# PAGE1.net
KiCad netlist of a schematic drawn in Altium Designer
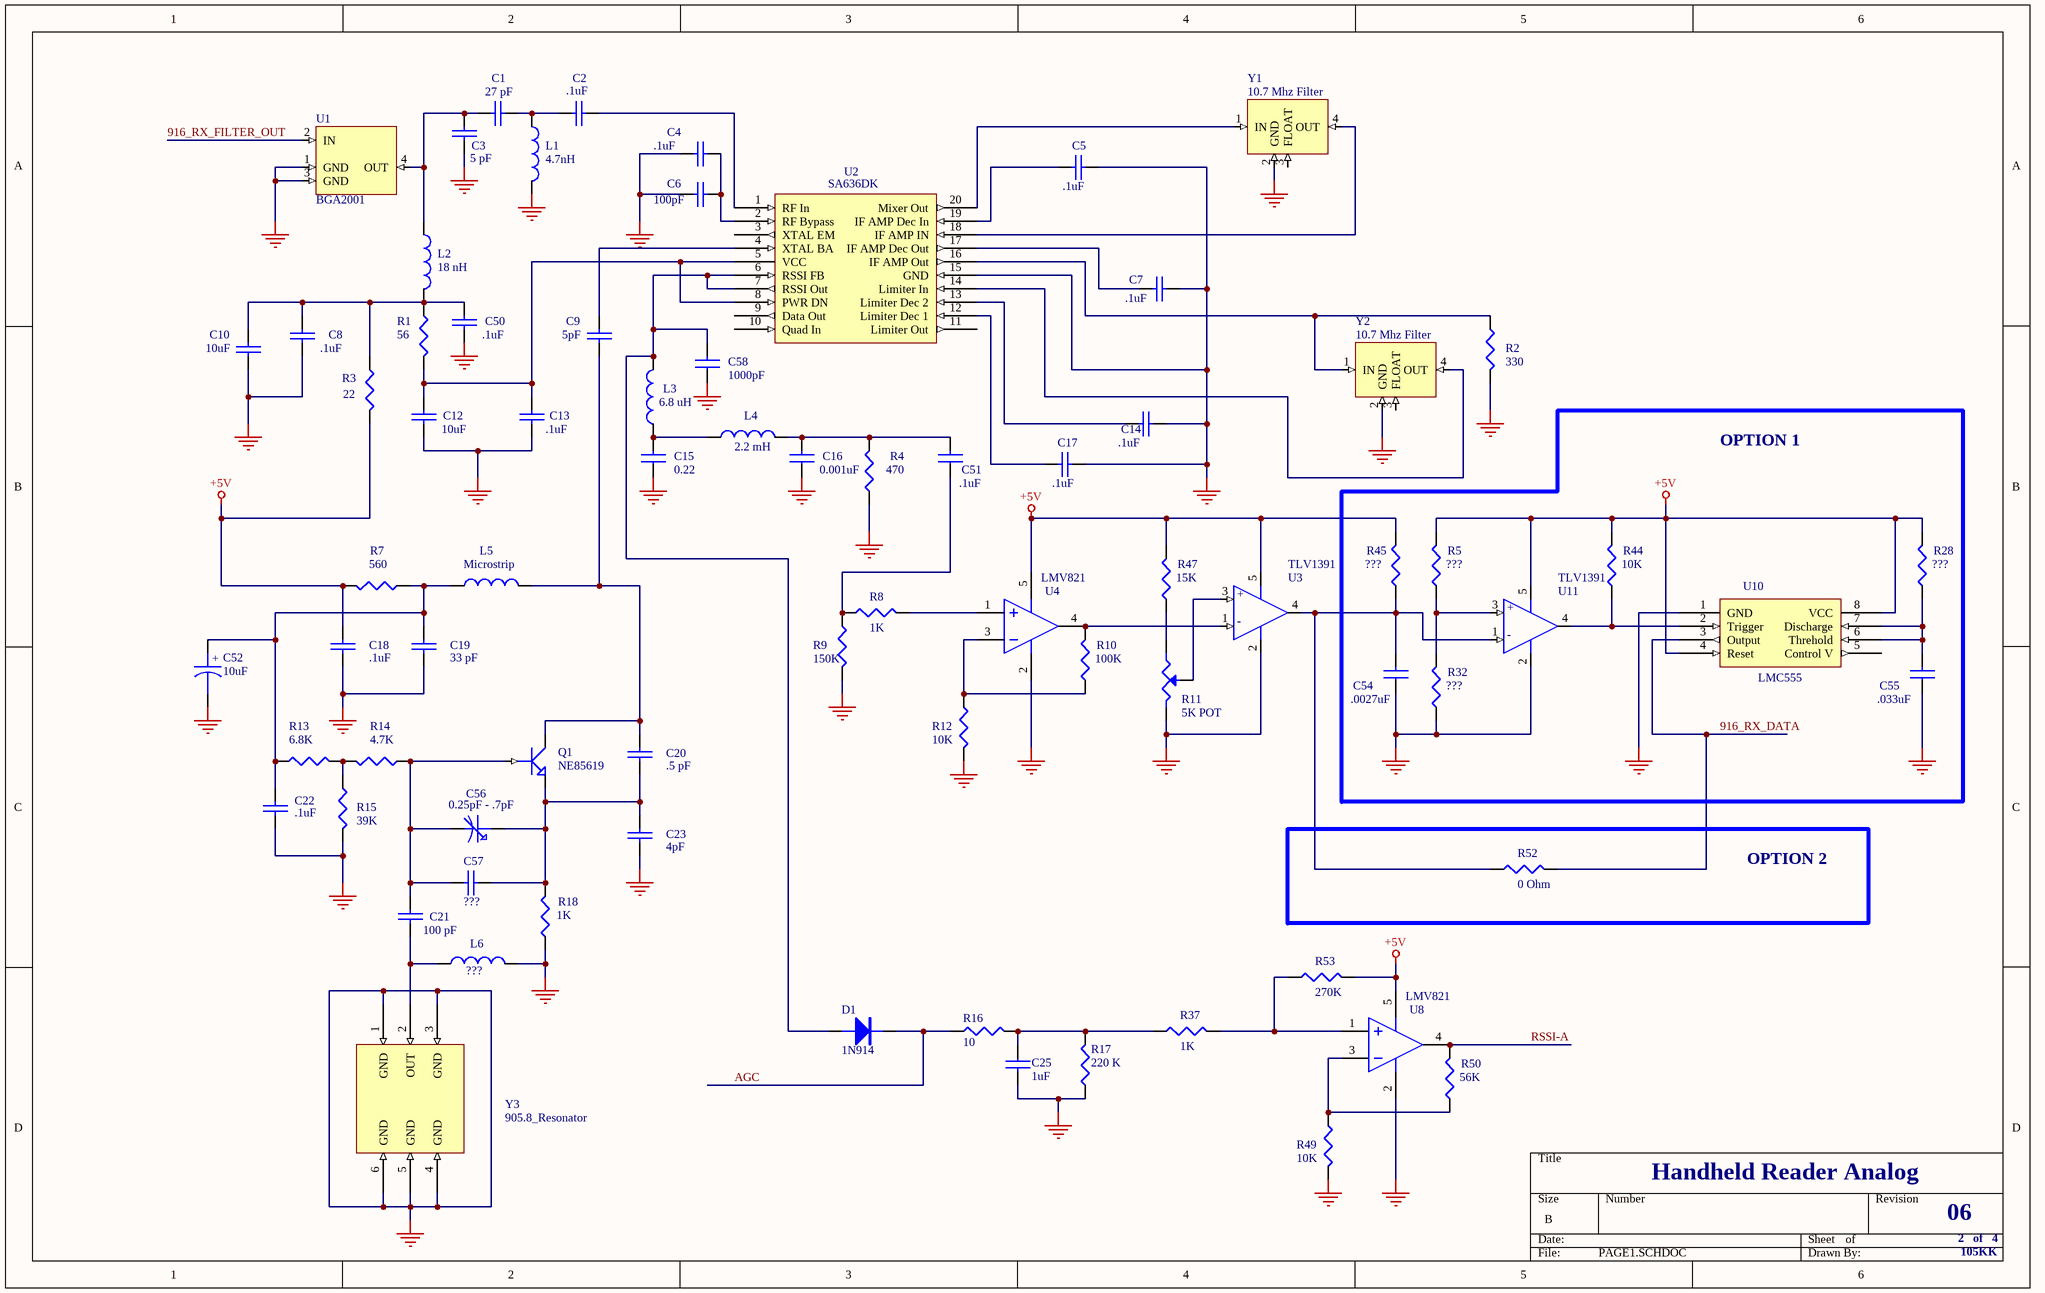
[diagram p0: PAGE1.SCHDOC]

(export (version "E")
  (design (tool "Eeschema 10.0.6"))
  (components
    (comp (ref "C1")
      (value "27 pF")
      (footprint "0603")
      (description "Capacitor")
      (libsource (lib "*") (part "CAP"))
    )
    (comp (ref "C2")
      (value ".1uF")
      (footprint "0603")
      (description "Capacitor")
      (libsource (lib "*") (part "CAP"))
    )
    (comp (ref "C3")
      (value "5 pF")
      (footprint "0603")
      (description "Capacitor")
      (libsource (lib "*") (part "CAP"))
    )
    (comp (ref "C4")
      (value ".1uF")
      (footprint "0603")
      (description "Capacitor")
      (libsource (lib "*") (part "CAP"))
    )
    (comp (ref "C5")
      (value ".1uF")
      (footprint "0603")
      (description "Capacitor")
      (libsource (lib "*") (part "CAP"))
    )
    (comp (ref "C6")
      (value "100pF")
      (footprint "0603")
      (description "Capacitor")
      (libsource (lib "*") (part "CAP"))
    )
    (comp (ref "C7")
      (value ".1uF")
      (footprint "0603")
      (description "Capacitor")
      (libsource (lib "*") (part "CAP"))
    )
    (comp (ref "C8")
      (value ".1uF")
      (footprint "0603")
      (description "Capacitor")
      (libsource (lib "*") (part "CAP"))
    )
    (comp (ref "C9")
      (value "5pF")
      (footprint "0603")
      (description "Capacitor")
      (libsource (lib "*") (part "CAP"))
    )
    (comp (ref "C10")
      (value "10uF")
      (footprint "CAP A CASE")
      (description "Capacitor")
      (libsource (lib "*") (part "CAP"))
    )
    (comp (ref "C12")
      (value "10uF")
      (footprint "CAP A CASE")
      (description "Capacitor")
      (libsource (lib "*") (part "CAP"))
    )
    (comp (ref "C13")
      (value ".1uF")
      (footprint "0603")
      (description "Capacitor")
      (libsource (lib "*") (part "CAP"))
    )
    (comp (ref "C14")
      (value ".1uF")
      (footprint "0603")
      (description "Capacitor")
      (libsource (lib "*") (part "CAP"))
    )
    (comp (ref "C15") (value "0.22") (footprint "0603") (libsource (lib "*") (part "CAP_NP")))
    (comp (ref "C16") (value "0.001uF") (footprint "0603") (libsource (lib "*") (part "CAP_NP")))
    (comp (ref "C17")
      (value ".1uF")
      (footprint "0603")
      (description "Capacitor")
      (libsource (lib "*") (part "CAP"))
    )
    (comp (ref "C18")
      (value ".1uF")
      (footprint "0603")
      (description "Capacitor")
      (libsource (lib "*") (part "CAP"))
    )
    (comp (ref "C19")
      (value "33 pF")
      (footprint "0603")
      (description "Capacitor")
      (libsource (lib "*") (part "CAP"))
    )
    (comp (ref "C20")
      (value ".5 pF")
      (footprint "0603")
      (description "Capacitor")
      (libsource (lib "*") (part "CAP"))
    )
    (comp (ref "C21")
      (value "100 pF")
      (footprint "0603")
      (description "Capacitor")
      (libsource (lib "*") (part "CAP"))
    )
    (comp (ref "C22")
      (value ".1uF")
      (footprint "0603")
      (description "Capacitor")
      (libsource (lib "*") (part "CAP"))
    )
    (comp (ref "C23")
      (value "4pF")
      (footprint "0603")
      (description "Capacitor")
      (libsource (lib "*") (part "CAP"))
    )
    (comp (ref "C25") (value "1uF") (footprint "CAP A CASE") (libsource (lib "*") (part "CAP_NP")))
    (comp (ref "C50")
      (value ".1uF")
      (footprint "0603")
      (description "Capacitor")
      (libsource (lib "*") (part "CAP"))
    )
    (comp (ref "C51") (value ".1uF") (footprint "0603") (libsource (lib "*") (part "CAP_NP")))
    (comp (ref "C52")
      (value "10uF")
      (footprint "CAP A CASE")
      (description "Capacitor")
      (libsource (lib "*") (part "CAPACITOR POL"))
    )
    (comp (ref "C54") (value ".0027uF") (footprint "0603") (libsource (lib "*") (part "CAP_NP")))
    (comp (ref "C55") (value ".033uF") (footprint "0805") (libsource (lib "*") (part "CAP_NP")))
    (comp (ref "C56")
      (value "0.25pF - .7pF")
      (footprint "CAP TRIMMER JOHANSON")
      (libsource (lib "*") (part "CAPACITOR VAR"))
    )
    (comp (ref "C57")
      (value "???")
      (footprint "0603")
      (description "Capacitor")
      (libsource (lib "*") (part "CAP"))
    )
    (comp (ref "C58") (value "1000pF") (footprint "0603") (libsource (lib "*") (part "CAP_NP")))
    (comp (ref "D1")
      (value "1N914")
      (footprint "SOT23 DIODE")
      (description "Diode")
      (libsource (lib "*") (part "DIODE"))
    )
    (comp (ref "L1") (value "4.7nH") (footprint "0603") (libsource (lib "*") (part "INDUCTOR")))
    (comp (ref "L2") (value "18 nH") (footprint "0603") (libsource (lib "*") (part "INDUCTOR")))
    (comp (ref "L3") (value "6.8 uH") (footprint "0805") (libsource (lib "*") (part "INDUCTOR")))
    (comp (ref "L4") (value "2.2 mH") (footprint "COIL TKS5540CT-ND") (libsource (lib "*") (part "INDUCTOR")))
    (comp (ref "L5") (value "Microstrip") (footprint "MICROSTRIP") (libsource (lib "*") (part "INDUCTOR")))
    (comp (ref "L6") (value "???") (footprint "0603") (libsource (lib "*") (part "INDUCTOR")))
    (comp (ref "Q1")
      (value "NE85619")
      (footprint "3 PIN ULTRA SUPER MINI MOLD")
      (description "NPN Transistor")
      (libsource (lib "*") (part "NPN1"))
    )
    (comp (ref "R1") (value "56") (footprint "0603") (libsource (lib "*") (part "R")))
    (comp (ref "R2") (value "330") (footprint "0603") (libsource (lib "*") (part "R")))
    (comp (ref "R3") (value "22") (footprint "0603") (libsource (lib "*") (part "R")))
    (comp (ref "R4") (value "470") (footprint "0603") (libsource (lib "*") (part "R")))
    (comp (ref "R5") (value "???") (footprint "0603") (libsource (lib "*") (part "R")))
    (comp (ref "R7") (value "560") (footprint "0603") (libsource (lib "*") (part "RESISTOR")))
    (comp (ref "R8") (value "1K") (footprint "0603") (libsource (lib "*") (part "R")))
    (comp (ref "R9") (value "150K") (footprint "0603") (libsource (lib "*") (part "R")))
    (comp (ref "R10") (value "100K") (footprint "0603") (libsource (lib "*") (part "R")))
    (comp (ref "R11")
      (value "5K POT")
      (footprint "POT PANA EVN5")
      (description "Potentiometer")
      (libsource (lib "*") (part "POT1"))
    )
    (comp (ref "R12") (value "10K") (footprint "0603") (libsource (lib "*") (part "R")))
    (comp (ref "R13") (value "6.8K") (footprint "0603") (libsource (lib "*") (part "RESISTOR")))
    (comp (ref "R14") (value "4.7K") (footprint "0603") (libsource (lib "*") (part "RESISTOR")))
    (comp (ref "R15") (value "39K") (footprint "0603") (libsource (lib "*") (part "RESISTOR")))
    (comp (ref "R16") (value "10") (footprint "0603") (libsource (lib "*") (part "R")))
    (comp (ref "R17") (value "220 K") (footprint "0603") (libsource (lib "*") (part "R")))
    (comp (ref "R18") (value "1K") (footprint "0603") (libsource (lib "*") (part "RESISTOR")))
    (comp (ref "R28") (value "???") (footprint "0603") (libsource (lib "*") (part "R")))
    (comp (ref "R32") (value "???") (footprint "0603") (libsource (lib "*") (part "R")))
    (comp (ref "R37") (value "1K") (footprint "0603") (libsource (lib "*") (part "R")))
    (comp (ref "R44") (value "10K") (footprint "0603") (libsource (lib "*") (part "R")))
    (comp (ref "R45") (value "???") (footprint "0603") (libsource (lib "*") (part "R")))
    (comp (ref "R47") (value "15K") (footprint "0603") (libsource (lib "*") (part "R")))
    (comp (ref "R49") (value "10K") (footprint "0603") (libsource (lib "*") (part "R")))
    (comp (ref "R50") (value "56K") (footprint "0603") (libsource (lib "*") (part "R")))
    (comp (ref "R52") (value "0 Ohm") (footprint "0603") (libsource (lib "*") (part "R")))
    (comp (ref "R53") (value "270K") (footprint "0603") (libsource (lib "*") (part "R")))
    (comp (ref "U1") (value "BGA2001") (footprint "SOT343") (libsource (lib "*") (part "BGA2001")))
    (comp (ref "U2") (value "SA636DK") (footprint "SSOP20") (libsource (lib "*") (part "SA636DK")))
    (comp (ref "U3") (value "TLV1391") (footprint "SOT25") (libsource (lib "*") (part "TLV1391")))
    (comp (ref "U4") (value "LMV821") (footprint "SOT25") (libsource (lib "*") (part "OPAMP1")))
    (comp (ref "U8") (value "LMV821") (footprint "SOT25") (libsource (lib "*") (part "OPAMP1")))
    (comp (ref "U10") (value "LMC555") (footprint "SO8 SMALL") (libsource (lib "*") (part "LMC555")))
    (comp (ref "U11") (value "TLV1391") (footprint "SOT25") (libsource (lib "*") (part "TLV1391")))
    (comp (ref "Y1") (value "10.7 Mhz Filter") (footprint "FILTER2") (libsource (lib "*") (part "FILTER2")))
    (comp (ref "Y2") (value "10.7 Mhz Filter") (footprint "FILTER2") (libsource (lib "*") (part "FILTER2")))
    (comp (ref "Y3")
      (value "905.8_Resonator")
      (footprint "RESONATOR2")
      (libsource (lib "*") (part "RESONATOR2"))
    )
  )
  (nets
    (net (code "1") (name "+5V") (class "Default")
      (node (ref "C18") (pin "1") (pinfunction "1_1") (pintype "passive"))
      (node (ref "R28") (pin "2") (pinfunction "2_2") (pintype "passive"))
      (node (ref "R3") (pin "2") (pinfunction "2_2") (pintype "passive"))
      (node (ref "R44") (pin "2") (pinfunction "2_2") (pintype "passive"))
      (node (ref "R45") (pin "2") (pinfunction "2_2") (pintype "passive"))
      (node (ref "R47") (pin "2") (pinfunction "2_2") (pintype "passive"))
      (node (ref "R5") (pin "2") (pinfunction "2_2") (pintype "passive"))
      (node (ref "R53") (pin "2") (pinfunction "2_2") (pintype "passive"))
      (node (ref "R7") (pin "2") (pinfunction "2_2") (pintype "passive"))
      (node (ref "U10") (pin "4") (pinfunction "Reset_4") (pintype "input"))
      (node (ref "U10") (pin "8") (pinfunction "VCC_8") (pintype "power_in"))
      (node (ref "U11") (pin "5") (pinfunction "VDD_5") (pintype "power_in"))
      (node (ref "U3") (pin "5") (pinfunction "VDD_5") (pintype "power_in"))
      (node (ref "U4") (pin "5") (pinfunction "5_5") (pintype "passive"))
      (node (ref "U8") (pin "5") (pinfunction "5_5") (pintype "passive"))
    )
    (net (code "2") (name "/916_RX_DATA") (class "Default")
      (node (ref "R52") (pin "2") (pinfunction "2_2") (pintype "passive"))
      (node (ref "U10") (pin "3") (pinfunction "Output_3") (pintype "output"))
    )
    (net (code "3") (name "/916_RX_FILTER_OUT") (class "Default")
      (node (ref "U1") (pin "2") (pinfunction "IN_2") (pintype "input"))
    )
    (net (code "4") (name "/AGC") (class "Default")
      (node (ref "D1") (pin "K") (pinfunction "K_K") (pintype "passive"))
      (node (ref "R16") (pin "2") (pinfunction "2_2") (pintype "passive"))
    )
    (net (code "5") (name "/RSSI-A") (class "Default")
      (node (ref "R50") (pin "2") (pinfunction "2_2") (pintype "passive"))
      (node (ref "U8") (pin "4") (pinfunction "4_4") (pintype "passive"))
    )
    (net (code "6") (name "GND_SIGNAL") (class "Default")
      (node (ref "C10") (pin "2") (pinfunction "2_2") (pintype "passive"))
      (node (ref "C12") (pin "2") (pinfunction "2_2") (pintype "passive"))
      (node (ref "C13") (pin "2") (pinfunction "2_2") (pintype "passive"))
      (node (ref "C14") (pin "2") (pinfunction "2_2") (pintype "passive"))
      (node (ref "C15") (pin "1") (pinfunction "1_1") (pintype "passive"))
      (node (ref "C16") (pin "1") (pinfunction "1_1") (pintype "passive"))
      (node (ref "C17") (pin "2") (pinfunction "2_2") (pintype "passive"))
      (node (ref "C18") (pin "2") (pinfunction "2_2") (pintype "passive"))
      (node (ref "C19") (pin "2") (pinfunction "2_2") (pintype "passive"))
      (node (ref "C22") (pin "2") (pinfunction "2_2") (pintype "passive"))
      (node (ref "C23") (pin "2") (pinfunction "2_2") (pintype "passive"))
      (node (ref "C25") (pin "2") (pinfunction "2_2") (pintype "passive"))
      (node (ref "C3") (pin "2") (pinfunction "2_2") (pintype "passive"))
      (node (ref "C4") (pin "1") (pinfunction "1_1") (pintype "passive"))
      (node (ref "C5") (pin "2") (pinfunction "2_2") (pintype "passive"))
      (node (ref "C50") (pin "2") (pinfunction "2_2") (pintype "passive"))
      (node (ref "C52") (pin "2") (pinfunction "2_2") (pintype "passive"))
      (node (ref "C54") (pin "1") (pinfunction "1_1") (pintype "passive"))
      (node (ref "C55") (pin "1") (pinfunction "1_1") (pintype "passive"))
      (node (ref "C58") (pin "1") (pinfunction "1_1") (pintype "passive"))
      (node (ref "C6") (pin "1") (pinfunction "1_1") (pintype "passive"))
      (node (ref "C7") (pin "2") (pinfunction "2_2") (pintype "passive"))
      (node (ref "C8") (pin "2") (pinfunction "2_2") (pintype "passive"))
      (node (ref "L1") (pin "2") (pinfunction "2_2") (pintype "passive"))
      (node (ref "L6") (pin "2") (pinfunction "2_2") (pintype "passive"))
      (node (ref "R11") (pin "3") (pinfunction "3_3") (pintype "passive"))
      (node (ref "R12") (pin "2") (pinfunction "2_2") (pintype "passive"))
      (node (ref "R15") (pin "2") (pinfunction "2_2") (pintype "passive"))
      (node (ref "R17") (pin "2") (pinfunction "2_2") (pintype "passive"))
      (node (ref "R18") (pin "1") (pinfunction "1_1") (pintype "passive"))
      (node (ref "R2") (pin "2") (pinfunction "2_2") (pintype "passive"))
      (node (ref "R32") (pin "1") (pinfunction "1_1") (pintype "passive"))
      (node (ref "R4") (pin "1") (pinfunction "1_1") (pintype "passive"))
      (node (ref "R49") (pin "2") (pinfunction "2_2") (pintype "passive"))
      (node (ref "R9") (pin "2") (pinfunction "2_2") (pintype "passive"))
      (node (ref "U1") (pin "1") (pinfunction "GND_1") (pintype "input"))
      (node (ref "U1") (pin "3") (pinfunction "GND_3") (pintype "input"))
      (node (ref "U10") (pin "1") (pinfunction "GND_1") (pintype "power_in"))
      (node (ref "U11") (pin "2") (pinfunction "VSS_2") (pintype "power_in"))
      (node (ref "U2") (pin "15") (pinfunction "GND_15") (pintype "input"))
      (node (ref "U3") (pin "2") (pinfunction "VSS_2") (pintype "power_in"))
      (node (ref "U4") (pin "2") (pinfunction "2_2") (pintype "passive"))
      (node (ref "U8") (pin "2") (pinfunction "2_2") (pintype "passive"))
      (node (ref "Y1") (pin "2") (pinfunction "GND_2") (pintype "input"))
      (node (ref "Y2") (pin "2") (pinfunction "GND_2") (pintype "input"))
      (node (ref "Y3") (pin "1") (pinfunction "GND_1") (pintype "input"))
      (node (ref "Y3") (pin "3") (pinfunction "GND_3") (pintype "input"))
      (node (ref "Y3") (pin "4") (pinfunction "GND_4") (pintype "input"))
      (node (ref "Y3") (pin "5") (pinfunction "GND_5") (pintype "input"))
      (node (ref "Y3") (pin "6") (pinfunction "GND_6") (pintype "input"))
    )
    (net (code "7") (name "Net-(C1-Pad2)") (class "Default")
      (node (ref "C1") (pin "2") (pinfunction "2_2") (pintype "passive"))
      (node (ref "C2") (pin "1") (pinfunction "1_1") (pintype "passive"))
      (node (ref "L1") (pin "1") (pinfunction "1_1") (pintype "passive"))
    )
    (net (code "8") (name "Net-(C10-Pad1)") (class "Default")
      (node (ref "C10") (pin "1") (pinfunction "1_1") (pintype "passive"))
      (node (ref "C50") (pin "1") (pinfunction "1_1") (pintype "passive"))
      (node (ref "C8") (pin "1") (pinfunction "1_1") (pintype "passive"))
      (node (ref "L2") (pin "2") (pinfunction "2_2") (pintype "passive"))
      (node (ref "R1") (pin "1") (pinfunction "1_1") (pintype "passive"))
      (node (ref "R3") (pin "1") (pinfunction "1_1") (pintype "passive"))
    )
    (net (code "9") (name "Net-(C15-Pad2)") (class "Default")
      (node (ref "C15") (pin "2") (pinfunction "2_2") (pintype "passive"))
      (node (ref "L3") (pin "1") (pinfunction "1_1") (pintype "passive"))
      (node (ref "L4") (pin "1") (pinfunction "1_1") (pintype "passive"))
    )
    (net (code "10") (name "Net-(C16-Pad2)") (class "Default")
      (node (ref "C16") (pin "2") (pinfunction "2_2") (pintype "passive"))
      (node (ref "C51") (pin "2") (pinfunction "2_2") (pintype "passive"))
      (node (ref "L4") (pin "2") (pinfunction "2_2") (pintype "passive"))
      (node (ref "R4") (pin "2") (pinfunction "2_2") (pintype "passive"))
    )
    (net (code "11") (name "Net-(C19-Pad1)") (class "Default")
      (node (ref "C19") (pin "1") (pinfunction "1_1") (pintype "passive"))
      (node (ref "C22") (pin "1") (pinfunction "1_1") (pintype "passive"))
      (node (ref "C52") (pin "1") (pinfunction "1_1") (pintype "passive"))
      (node (ref "L5") (pin "1") (pinfunction "1_1") (pintype "passive"))
      (node (ref "R13") (pin "1") (pinfunction "1_1") (pintype "passive"))
      (node (ref "R7") (pin "1") (pinfunction "1_1") (pintype "passive"))
    )
    (net (code "12") (name "Net-(C20-Pad1)") (class "Default")
      (node (ref "C20") (pin "1") (pinfunction "1_1") (pintype "passive"))
      (node (ref "C9") (pin "1") (pinfunction "1_1") (pintype "passive"))
      (node (ref "L5") (pin "2") (pinfunction "2_2") (pintype "passive"))
      (node (ref "Q1") (pin "C") (pinfunction "C_C") (pintype "passive"))
    )
    (net (code "13") (name "Net-(C20-Pad2)") (class "Default")
      (node (ref "C20") (pin "2") (pinfunction "2_2") (pintype "passive"))
      (node (ref "C23") (pin "1") (pinfunction "1_1") (pintype "passive"))
      (node (ref "C56") (pin "1") (pinfunction "1_1") (pintype "passive"))
      (node (ref "C57") (pin "2") (pinfunction "2_2") (pintype "passive"))
      (node (ref "Q1") (pin "E") (pinfunction "E_E") (pintype "passive"))
      (node (ref "R18") (pin "2") (pinfunction "2_2") (pintype "passive"))
    )
    (net (code "14") (name "Net-(C21-Pad1)") (class "Default")
      (node (ref "C21") (pin "1") (pinfunction "1_1") (pintype "passive"))
      (node (ref "C56") (pin "2") (pinfunction "2_2") (pintype "passive"))
      (node (ref "C57") (pin "1") (pinfunction "1_1") (pintype "passive"))
      (node (ref "Q1") (pin "B") (pinfunction "B_B") (pintype "input"))
      (node (ref "R14") (pin "1") (pinfunction "1_1") (pintype "passive"))
    )
    (net (code "15") (name "Net-(C25-Pad1)") (class "Default")
      (node (ref "C25") (pin "1") (pinfunction "1_1") (pintype "passive"))
      (node (ref "R16") (pin "1") (pinfunction "1_1") (pintype "passive"))
      (node (ref "R17") (pin "1") (pinfunction "1_1") (pintype "passive"))
      (node (ref "R37") (pin "1") (pinfunction "1_1") (pintype "passive"))
    )
    (net (code "16") (name "Net-(C51-Pad1)") (class "Default")
      (node (ref "C51") (pin "1") (pinfunction "1_1") (pintype "passive"))
      (node (ref "R8") (pin "1") (pinfunction "1_1") (pintype "passive"))
      (node (ref "R9") (pin "1") (pinfunction "1_1") (pintype "passive"))
    )
    (net (code "17") (name "Net-(R8-Pad2)") (class "Default")
      (node (ref "R8") (pin "2") (pinfunction "2_2") (pintype "passive"))
      (node (ref "U4") (pin "1") (pinfunction "1_1") (pintype "passive"))
    )
    (net (code "18") (name "Net-(R10-Pad1)") (class "Default")
      (node (ref "R10") (pin "1") (pinfunction "1_1") (pintype "passive"))
      (node (ref "R12") (pin "1") (pinfunction "1_1") (pintype "passive"))
      (node (ref "U4") (pin "3") (pinfunction "3_3") (pintype "passive"))
    )
    (net (code "19") (name "Net-(R11-Pad1)") (class "Default")
      (node (ref "R11") (pin "1") (pinfunction "1_1") (pintype "passive"))
      (node (ref "R47") (pin "1") (pinfunction "1_1") (pintype "passive"))
    )
    (net (code "20") (name "Net-(R13-Pad2)") (class "Default")
      (node (ref "R13") (pin "2") (pinfunction "2_2") (pintype "passive"))
      (node (ref "R14") (pin "2") (pinfunction "2_2") (pintype "passive"))
      (node (ref "R15") (pin "1") (pinfunction "1_1") (pintype "passive"))
    )
    (net (code "21") (name "Net-(R37-Pad2)") (class "Default")
      (node (ref "R37") (pin "2") (pinfunction "2_2") (pintype "passive"))
      (node (ref "R53") (pin "1") (pinfunction "1_1") (pintype "passive"))
      (node (ref "U8") (pin "1") (pinfunction "1_1") (pintype "passive"))
    )
    (net (code "22") (name "Net-(R49-Pad1)") (class "Default")
      (node (ref "R49") (pin "1") (pinfunction "1_1") (pintype "passive"))
      (node (ref "R50") (pin "1") (pinfunction "1_1") (pintype "passive"))
      (node (ref "U8") (pin "3") (pinfunction "3_3") (pintype "passive"))
    )
    (net (code "23") (name "Net-(U1-OUT)") (class "Default")
      (node (ref "C1") (pin "1") (pinfunction "1_1") (pintype "passive"))
      (node (ref "C3") (pin "1") (pinfunction "1_1") (pintype "passive"))
      (node (ref "L2") (pin "1") (pinfunction "1_1") (pintype "passive"))
      (node (ref "U1") (pin "4") (pinfunction "OUT_4") (pintype "input"))
    )
    (net (code "24") (name "Net-(U2-IF_AMP_Dec_In)") (class "Default")
      (node (ref "C5") (pin "1") (pinfunction "1_1") (pintype "passive"))
      (node (ref "U2") (pin "19") (pinfunction "IF_AMP_Dec_In_19") (pintype "input"))
    )
    (net (code "25") (name "Net-(U2-IF_AMP_Dec_Out)") (class "Default")
      (node (ref "C7") (pin "1") (pinfunction "1_1") (pintype "passive"))
      (node (ref "U2") (pin "17") (pinfunction "IF_AMP_Dec_Out_17") (pintype "output"))
    )
    (net (code "26") (name "Net-(U2-IF_AMP_IN)") (class "Default")
      (node (ref "U2") (pin "18") (pinfunction "IF_AMP_IN_18") (pintype "input"))
      (node (ref "Y1") (pin "4") (pinfunction "OUT_4") (pintype "input"))
    )
    (net (code "27") (name "Net-(U2-IF_AMP_Out)") (class "Default")
      (node (ref "R2") (pin "1") (pinfunction "1_1") (pintype "passive"))
      (node (ref "U2") (pin "16") (pinfunction "IF_AMP_Out_16") (pintype "output"))
      (node (ref "Y2") (pin "1") (pinfunction "IN_1") (pintype "input"))
    )
    (net (code "28") (name "Net-(U2-Limiter_Dec_1)") (class "Default")
      (node (ref "C17") (pin "1") (pinfunction "1_1") (pintype "passive"))
      (node (ref "U2") (pin "12") (pinfunction "Limiter_Dec_1_12") (pintype "input"))
    )
    (net (code "29") (name "Net-(U2-Limiter_Dec_2)") (class "Default")
      (node (ref "C14") (pin "1") (pinfunction "1_1") (pintype "passive"))
      (node (ref "U2") (pin "13") (pinfunction "Limiter_Dec_2_13") (pintype "input"))
    )
    (net (code "30") (name "Net-(U2-Limiter_In)") (class "Default")
      (node (ref "U2") (pin "14") (pinfunction "Limiter_In_14") (pintype "input"))
      (node (ref "Y2") (pin "4") (pinfunction "OUT_4") (pintype "input"))
    )
    (net (code "31") (name "Net-(U2-Mixer_Out)") (class "Default")
      (node (ref "U2") (pin "20") (pinfunction "Mixer_Out_20") (pintype "output"))
      (node (ref "Y1") (pin "1") (pinfunction "IN_1") (pintype "input"))
    )
    (net (code "32") (name "Net-(U2-PWR_DN)") (class "Default")
      (node (ref "C12") (pin "1") (pinfunction "1_1") (pintype "passive"))
      (node (ref "C13") (pin "1") (pinfunction "1_1") (pintype "passive"))
      (node (ref "R1") (pin "2") (pinfunction "2_2") (pintype "passive"))
      (node (ref "U2") (pin "5") (pinfunction "VCC_5") (pintype "power_in"))
      (node (ref "U2") (pin "8") (pinfunction "PWR_DN_8") (pintype "input"))
    )
    (net (code "33") (name "Net-(U2-RF_Bypass)") (class "Default")
      (node (ref "C4") (pin "2") (pinfunction "2_2") (pintype "passive"))
      (node (ref "C6") (pin "2") (pinfunction "2_2") (pintype "passive"))
      (node (ref "U2") (pin "2") (pinfunction "RF_Bypass_2") (pintype "input"))
    )
    (net (code "34") (name "Net-(U2-RF_In)") (class "Default")
      (node (ref "C2") (pin "2") (pinfunction "2_2") (pintype "passive"))
      (node (ref "U2") (pin "1") (pinfunction "RF_In_1") (pintype "input"))
    )
    (net (code "35") (name "Net-(U2-RSSI_FB)") (class "Default")
      (node (ref "C58") (pin "2") (pinfunction "2_2") (pintype "passive"))
      (node (ref "D1") (pin "A") (pinfunction "A_A") (pintype "passive"))
      (node (ref "L3") (pin "2") (pinfunction "2_2") (pintype "passive"))
      (node (ref "U2") (pin "6") (pinfunction "RSSI_FB_6") (pintype "input"))
      (node (ref "U2") (pin "7") (pinfunction "RSSI_Out_7") (pintype "output"))
    )
    (net (code "36") (name "Net-(U2-XTAL_BA)") (class "Default")
      (node (ref "C9") (pin "2") (pinfunction "2_2") (pintype "passive"))
      (node (ref "U2") (pin "4") (pinfunction "XTAL_BA_4") (pintype "input"))
    )
    (net (code "37") (name "Net-(U3-+)") (class "Default")
      (node (ref "R11") (pin "2") (pinfunction "2_2") (pintype "passive"))
      (node (ref "U3") (pin "3") (pinfunction "+_3") (pintype "input"))
    )
    (net (code "38") (name "Net-(U3--)") (class "Default")
      (node (ref "R10") (pin "2") (pinfunction "2_2") (pintype "passive"))
      (node (ref "U3") (pin "1") (pinfunction "-_1") (pintype "input"))
      (node (ref "U4") (pin "4") (pinfunction "4_4") (pintype "passive"))
    )
    (net (code "39") (name "Net-(U10-Discharge)") (class "Default")
      (node (ref "C55") (pin "2") (pinfunction "2_2") (pintype "passive"))
      (node (ref "R28") (pin "1") (pinfunction "1_1") (pintype "passive"))
      (node (ref "U10") (pin "6") (pinfunction "Threhold_6") (pintype "input"))
      (node (ref "U10") (pin "7") (pinfunction "Discharge_7") (pintype "input"))
    )
    (net (code "40") (name "Net-(U10-Trigger)") (class "Default")
      (node (ref "R44") (pin "1") (pinfunction "1_1") (pintype "passive"))
      (node (ref "U10") (pin "2") (pinfunction "Trigger_2") (pintype "input"))
      (node (ref "U11") (pin "4") (pinfunction "OUT_4") (pintype "open_collector"))
    )
    (net (code "41") (name "Net-(U11-+)") (class "Default")
      (node (ref "R32") (pin "2") (pinfunction "2_2") (pintype "passive"))
      (node (ref "R5") (pin "1") (pinfunction "1_1") (pintype "passive"))
      (node (ref "U11") (pin "3") (pinfunction "+_3") (pintype "input"))
    )
    (net (code "42") (name "Net-(U11--)") (class "Default")
      (node (ref "C54") (pin "2") (pinfunction "2_2") (pintype "passive"))
      (node (ref "R45") (pin "1") (pinfunction "1_1") (pintype "passive"))
      (node (ref "R52") (pin "1") (pinfunction "1_1") (pintype "passive"))
      (node (ref "U11") (pin "1") (pinfunction "-_1") (pintype "input"))
      (node (ref "U3") (pin "4") (pinfunction "OUT_4") (pintype "open_collector"))
    )
    (net (code "43") (name "Net-(Y3-OUT)") (class "Default")
      (node (ref "C21") (pin "2") (pinfunction "2_2") (pintype "passive"))
      (node (ref "L6") (pin "1") (pinfunction "1_1") (pintype "passive"))
      (node (ref "Y3") (pin "2") (pinfunction "OUT_2") (pintype "input"))
    )
    (net (code "44") (name "unconnected-(U2-Data_Out-Pad9)") (class "Default")
      (node (ref "U2") (pin "9") (pinfunction "Data_Out_9") (pintype "output"))
    )
    (net (code "45") (name "unconnected-(U2-Limiter_Out-Pad11)") (class "Default")
      (node (ref "U2") (pin "11") (pinfunction "Limiter_Out_11") (pintype "output"))
    )
    (net (code "46") (name "unconnected-(U2-Quad_In-Pad10)") (class "Default")
      (node (ref "U2") (pin "10") (pinfunction "Quad_In_10") (pintype "input"))
    )
    (net (code "47") (name "unconnected-(U2-XTAL_EM-Pad3)") (class "Default")
      (node (ref "U2") (pin "3") (pinfunction "XTAL_EM_3") (pintype "output"))
    )
    (net (code "48") (name "unconnected-(U10-Control_V-Pad5)") (class "Default")
      (node (ref "U10") (pin "5") (pinfunction "Control_V_5") (pintype "output"))
    )
    (net (code "49") (name "unconnected-(Y1-FLOAT-Pad3)") (class "Default")
      (node (ref "Y1") (pin "3") (pinfunction "FLOAT_3") (pintype "input"))
    )
    (net (code "50") (name "unconnected-(Y2-FLOAT-Pad3)") (class "Default")
      (node (ref "Y2") (pin "3") (pinfunction "FLOAT_3") (pintype "input"))
    )
  )
)
